# schematicdesign.net
KiCad netlist of a schematic drawn in EasyEDA
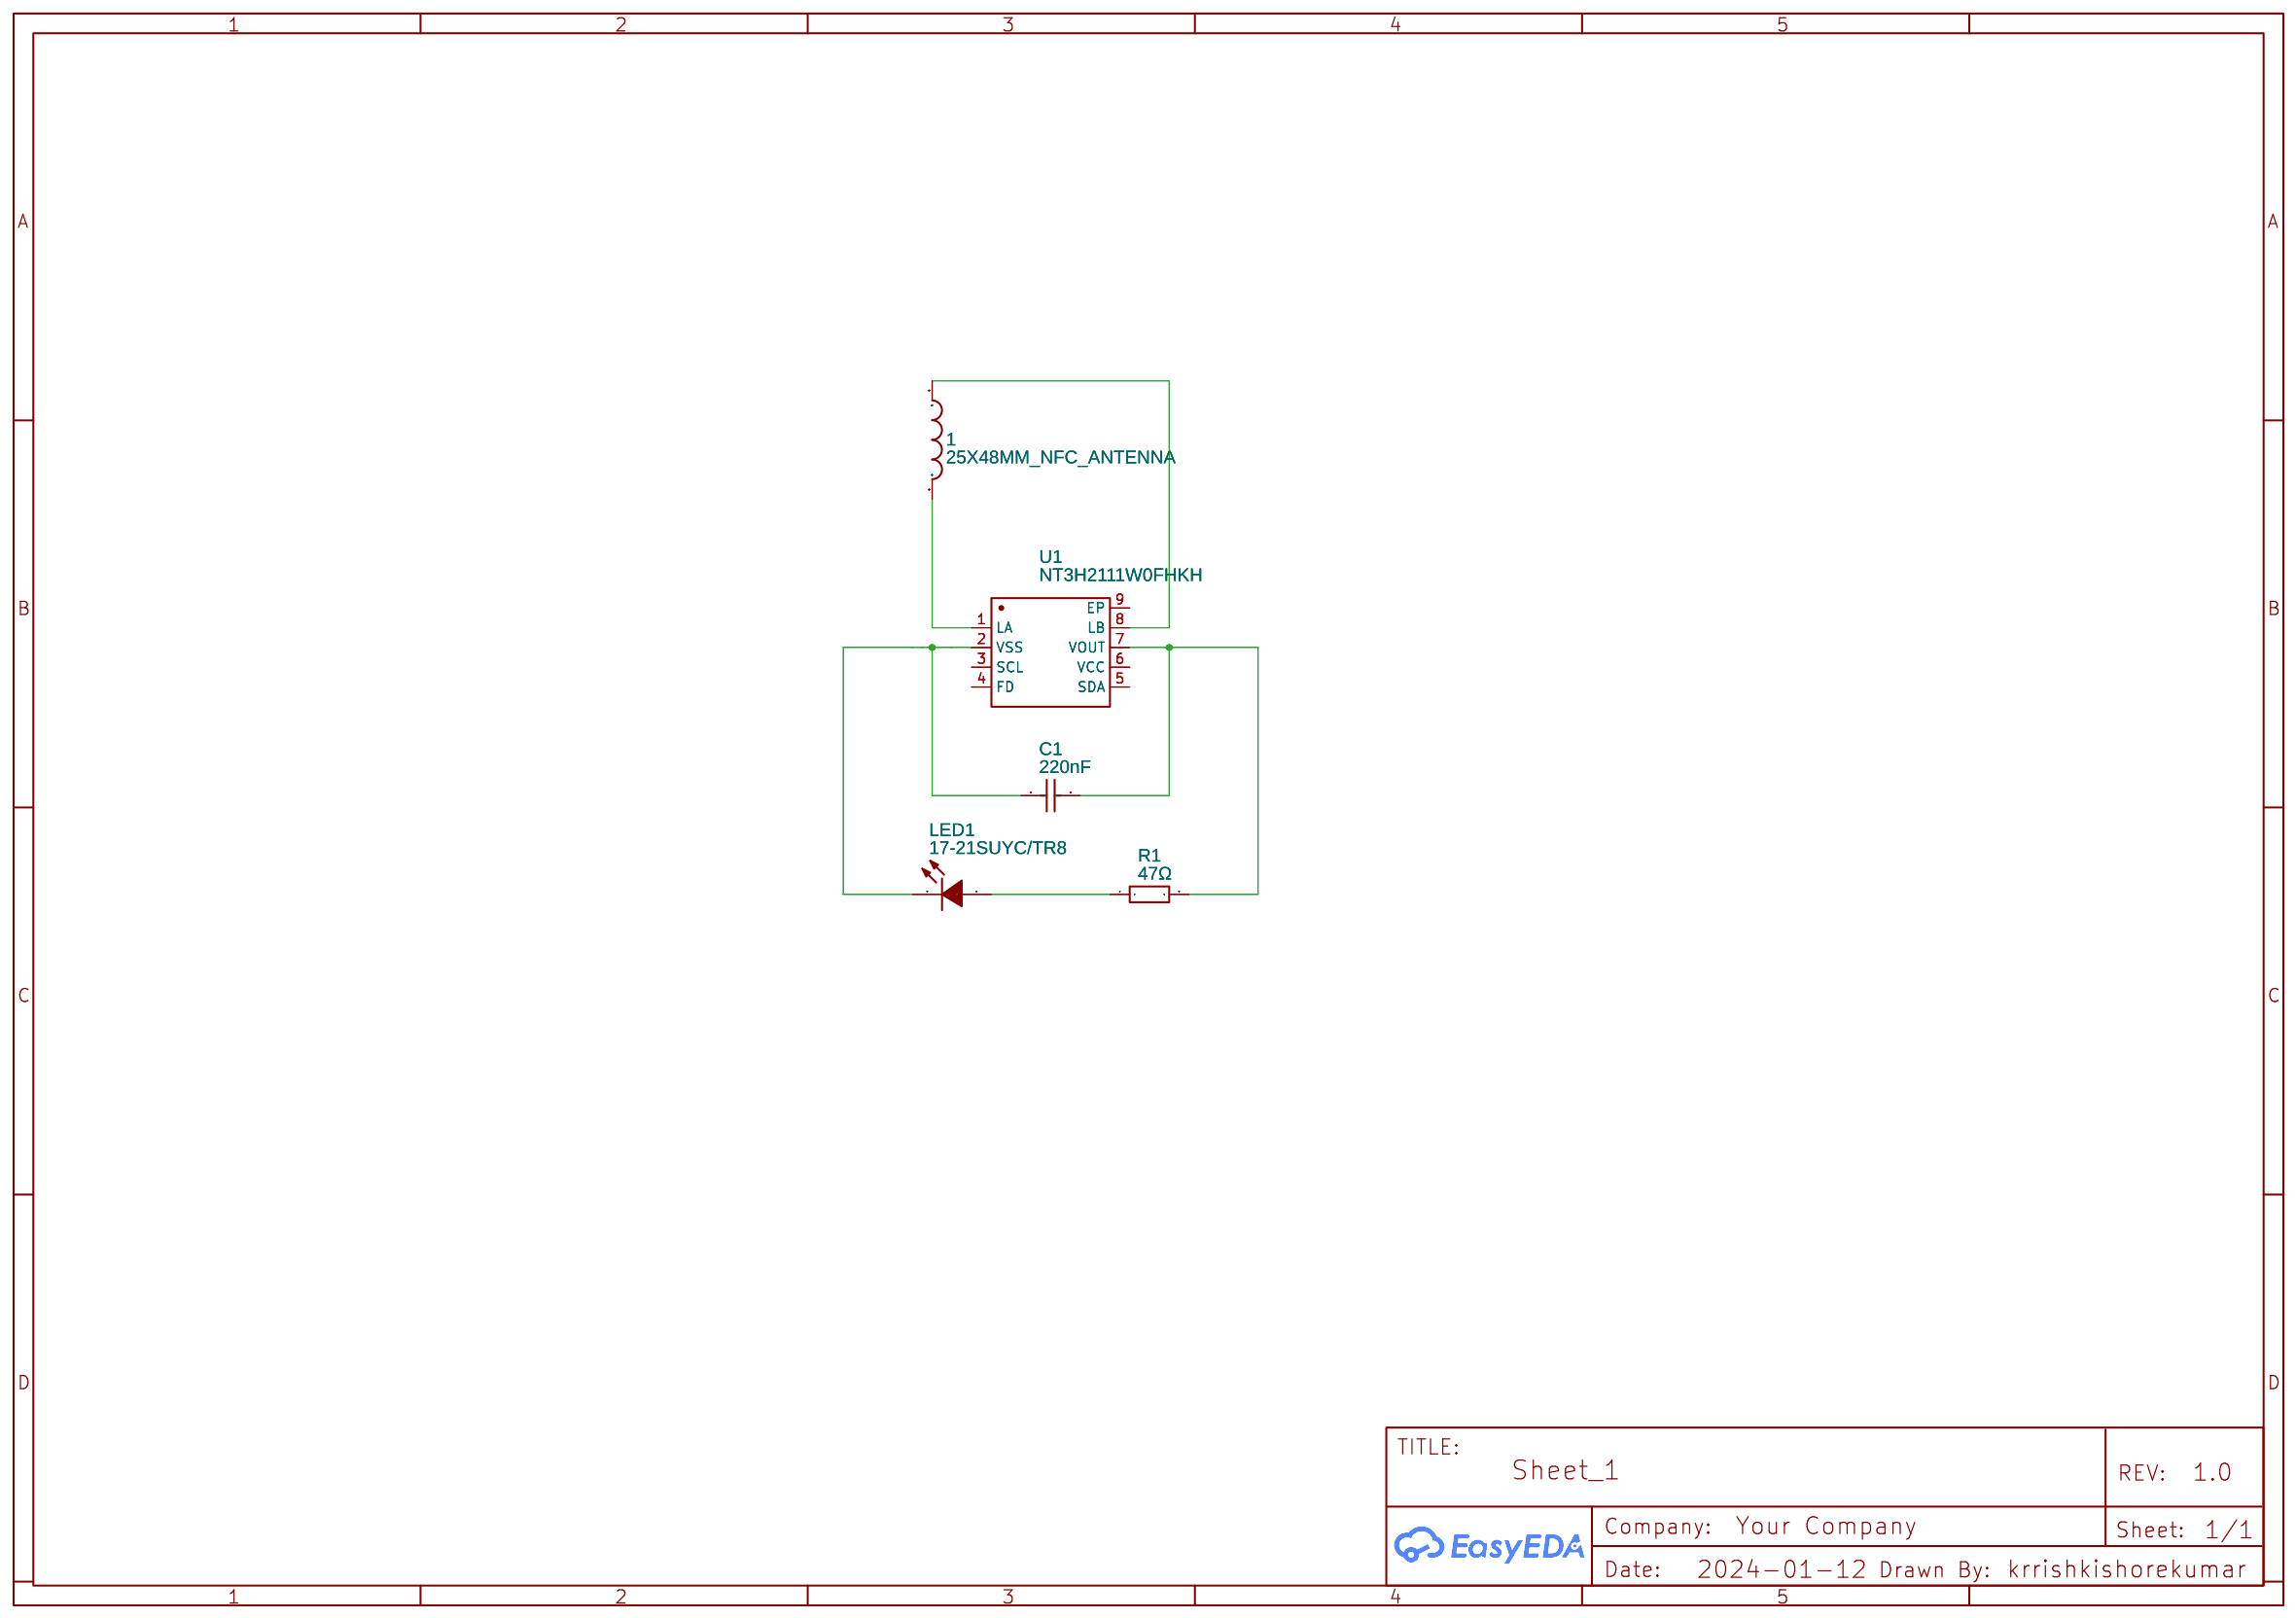
[diagram p0: schematic sheet]

(export (version "E")
  (design (tool "Eeschema 10.0.6"))
  (components
    (comp (ref "1") (value "25X48MM_NFC_ANTENNA") (libsource (lib "") (part "25X48MM_NFC_ANTENNA")))
    (comp (ref "C1")
      (value "220nF")
      (fields
        (field (name "Manufacturer Part") "CL10B224KA8NNNC")
        (field (name "Manufacturer") "SAMSUNG(三星)")
      )
      (libsource (lib "") (part "CL10B224KA8NNNC"))
    )
    (comp (ref "LED1")
      (value "17-21SUYC/TR8")
      (fields (field (name "Manufacturer Part") "KT-0805黄灯") (field (name "Manufacturer") "KENTO"))
      (libsource (lib "") (part "17-21SUYC/TR8"))
    )
    (comp (ref "R1")
      (value "47Ω")
      (fields
        (field (name "Manufacturer Part") "0603WAF470JT5E")
        (field (name "Manufacturer") "UNI-ROYAL(厚声)")
      )
      (libsource (lib "") (part "0603WAF470JT5E"))
    )
    (comp (ref "U1")
      (value "NT3H2111W0FHKH")
      (fields (field (name "Manufacturer") "NXP(恩智浦)"))
      (libsource (lib "") (part "NT3H2111W0FHKH"))
    )
  )
  (nets
    (net (code "1") (name "Net-(LED1-+)") (class "Default")
      (node (ref "LED1") (pin "1") (pinfunction "+_1") (pintype "unspecified"))
      (node (ref "R1") (pin "1") (pinfunction "1_1") (pintype "input"))
    )
    (net (code "2") (name "Net-(LED1--)") (class "Default")
      (node (ref "C1") (pin "1") (pinfunction "1_1") (pintype "input"))
      (node (ref "LED1") (pin "2") (pinfunction "-_2") (pintype "unspecified"))
      (node (ref "U1") (pin "2") (pinfunction "VSS_2") (pintype "unspecified"))
    )
    (net (code "3") (name "Net-(U1-LA)") (class "Default")
      (node (ref "1") (pin "P$2") (pinfunction "P$2_P$2") (pintype "bidirectional"))
      (node (ref "U1") (pin "1") (pinfunction "LA_1") (pintype "unspecified"))
    )
    (net (code "4") (name "Net-(U1-LB)") (class "Default")
      (node (ref "1") (pin "P$1") (pinfunction "P$1_P$1") (pintype "bidirectional"))
      (node (ref "U1") (pin "8") (pinfunction "LB_8") (pintype "unspecified"))
    )
    (net (code "5") (name "Net-(U1-VOUT)") (class "Default")
      (node (ref "C1") (pin "2") (pinfunction "2_2") (pintype "input"))
      (node (ref "R1") (pin "2") (pinfunction "2_2") (pintype "input"))
      (node (ref "U1") (pin "7") (pinfunction "VOUT_7") (pintype "unspecified"))
    )
    (net (code "6") (name "unconnected-(U1-EP-Pad9)") (class "Default")
      (node (ref "U1") (pin "9") (pinfunction "EP_9") (pintype "unspecified"))
    )
    (net (code "7") (name "unconnected-(U1-FD-Pad4)") (class "Default")
      (node (ref "U1") (pin "4") (pinfunction "FD_4") (pintype "unspecified"))
    )
    (net (code "8") (name "unconnected-(U1-SCL-Pad3)") (class "Default")
      (node (ref "U1") (pin "3") (pinfunction "SCL_3") (pintype "unspecified"))
    )
    (net (code "9") (name "unconnected-(U1-SDA-Pad5)") (class "Default")
      (node (ref "U1") (pin "5") (pinfunction "SDA_5") (pintype "unspecified"))
    )
    (net (code "10") (name "unconnected-(U1-VCC-Pad6)") (class "Default")
      (node (ref "U1") (pin "6") (pinfunction "VCC_6") (pintype "unspecified"))
    )
  )
)
